# OpenBookReaderC_v26.net
KiCad netlist of a schematic drawn in EAGLE
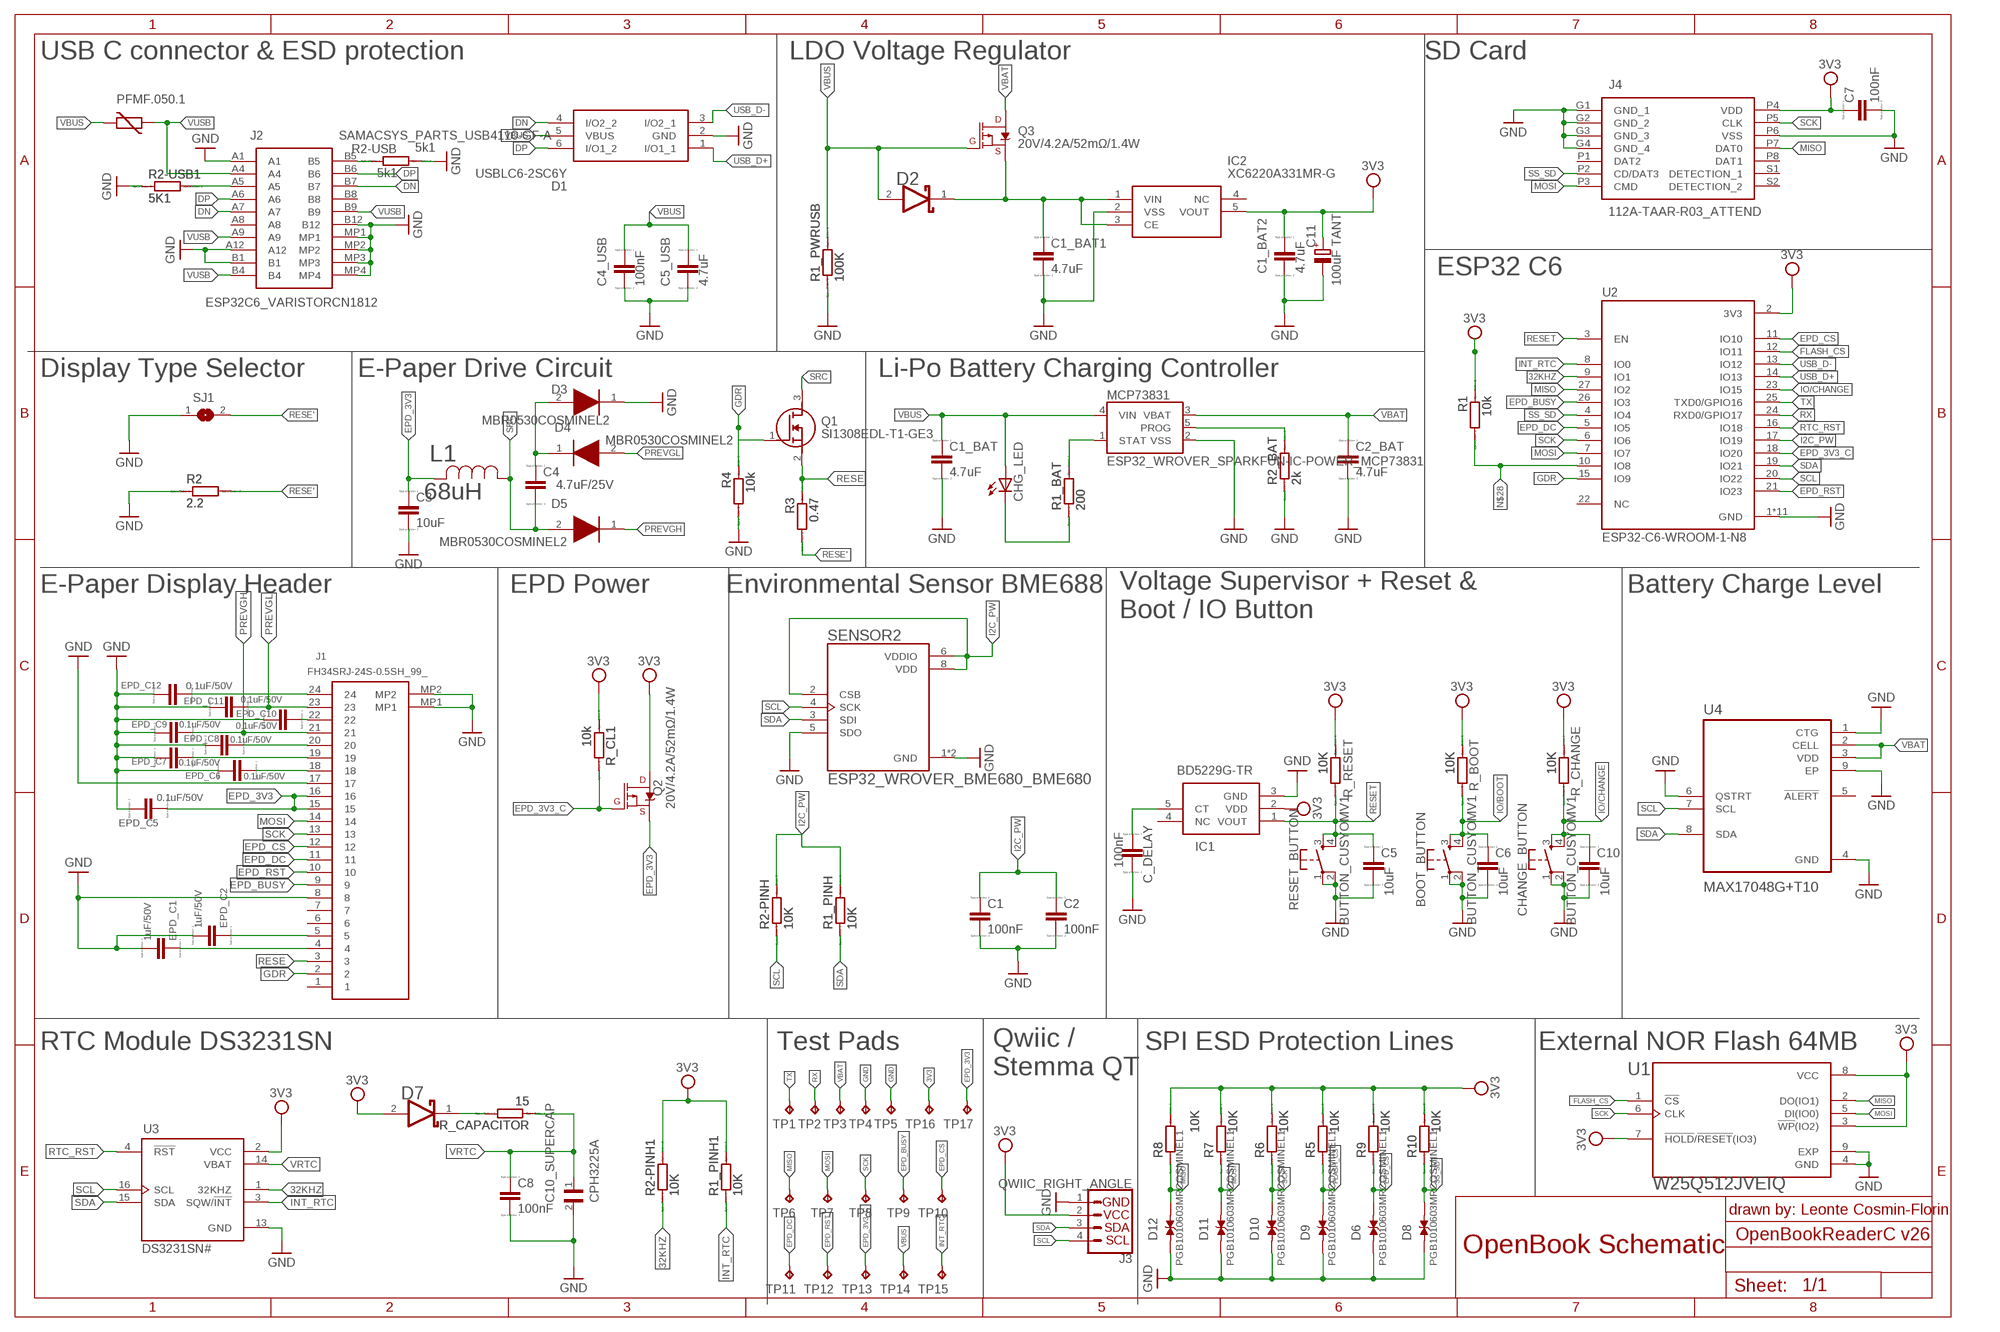
[diagram p0: schematic, sheet 1]

(export (version "E")
  (design (tool "Eeschema 10.0.6"))
  (components
    (comp (ref "BOOT_BUTTON")
      (value "BUTTON_CUSYOMV1")
      (footprint "eagle-import:MYBUTTON")
      (libsource (lib "eagle-import") (part "BUTTON_CUSYOMV1"))
    )
    (comp (ref "C1")
      (value "100nF")
      (footprint "eagle-import:ESP32_WROVER_EAGLE-LTSPICE_C0402")
      (libsource (lib "eagle-import") (part "ESP32_WROVER_EAGLE-LTSPICE_C"))
    )
    (comp (ref "C1_BAT")
      (value "4.7uF")
      (footprint "eagle-import:ESP32_WROVER_EAGLE-LTSPICE_C0402")
      (libsource (lib "eagle-import") (part "ESP32_WROVER_EAGLE-LTSPICE_C"))
    )
    (comp (ref "C1_BAT1")
      (value "4.7uF")
      (footprint "eagle-import:ESP32_WROVER_EAGLE-LTSPICE_C0402")
      (libsource (lib "eagle-import") (part "ESP32_WROVER_EAGLE-LTSPICE_C"))
    )
    (comp (ref "C1_BAT2")
      (value "4.7uF")
      (footprint "eagle-import:ESP32_WROVER_EAGLE-LTSPICE_C0402")
      (libsource (lib "eagle-import") (part "ESP32_WROVER_EAGLE-LTSPICE_C"))
    )
    (comp (ref "C2")
      (value "100nF")
      (footprint "eagle-import:ESP32_WROVER_EAGLE-LTSPICE_C0402")
      (libsource (lib "eagle-import") (part "ESP32_WROVER_EAGLE-LTSPICE_C"))
    )
    (comp (ref "C2_BAT")
      (value "4.7uF")
      (footprint "eagle-import:ESP32_WROVER_EAGLE-LTSPICE_C0402")
      (libsource (lib "eagle-import") (part "ESP32_WROVER_EAGLE-LTSPICE_C"))
    )
    (comp (ref "C3")
      (value "10uF")
      (footprint "eagle-import:ESP32_WROVER_EAGLE-LTSPICE_C0402")
      (libsource (lib "eagle-import") (part "ESP32_WROVER_EAGLE-LTSPICE_C"))
    )
    (comp (ref "C4")
      (value "4.7uF/25V")
      (footprint "eagle-import:ESP32_WROVER_EAGLE-LTSPICE_C0402")
      (libsource (lib "eagle-import") (part "ESP32_WROVER_EAGLE-LTSPICE_CC0402"))
    )
    (comp (ref "C4_USB")
      (value "100nF")
      (footprint "eagle-import:ESP32_WROVER_EAGLE-LTSPICE_C0402")
      (libsource (lib "eagle-import") (part "ESP32_WROVER_EAGLE-LTSPICE_C"))
    )
    (comp (ref "C5")
      (value "10uF")
      (footprint "eagle-import:ESP32_WROVER_EAGLE-LTSPICE_C0402")
      (libsource (lib "eagle-import") (part "ESP32_WROVER_EAGLE-LTSPICE_C"))
    )
    (comp (ref "C5_USB")
      (value "4.7uF")
      (footprint "eagle-import:ESP32_WROVER_EAGLE-LTSPICE_C0402")
      (libsource (lib "eagle-import") (part "ESP32_WROVER_EAGLE-LTSPICE_C"))
    )
    (comp (ref "C6")
      (value "10uF")
      (footprint "eagle-import:ESP32_WROVER_EAGLE-LTSPICE_C0402")
      (libsource (lib "eagle-import") (part "ESP32_WROVER_EAGLE-LTSPICE_C"))
    )
    (comp (ref "C7")
      (value "100nF")
      (footprint "eagle-import:ESP32_WROVER_EAGLE-LTSPICE_C0402")
      (libsource (lib "eagle-import") (part "ESP32_WROVER_EAGLE-LTSPICE_C"))
    )
    (comp (ref "C8")
      (value "100nF")
      (footprint "eagle-import:ESP32_WROVER_EAGLE-LTSPICE_C0402")
      (libsource (lib "eagle-import") (part "ESP32_WROVER_EAGLE-LTSPICE_C"))
    )
    (comp (ref "C10")
      (value "10uF")
      (footprint "eagle-import:ESP32_WROVER_EAGLE-LTSPICE_C0402")
      (libsource (lib "eagle-import") (part "ESP32_WROVER_EAGLE-LTSPICE_C"))
    )
    (comp (ref "C10_SUPERCAP")
      (value "CPH3225A")
      (footprint "eagle-import:CAPCP3225X100N")
      (fields (field (name "MF") "Seiko Instruments"))
      (libsource (lib "eagle-import") (part "CPH3225A"))
    )
    (comp (ref "C11")
      (value "100uF TANT")
      (footprint "eagle-import:RCL_CT3528")
      (libsource (lib "eagle-import") (part "RCL_CPOL-EUCT3528"))
    )
    (comp (ref "CHANGE_BUTTON")
      (value "BUTTON_CUSYOMV1")
      (footprint "eagle-import:MYBUTTON")
      (libsource (lib "eagle-import") (part "BUTTON_CUSYOMV1"))
    )
    (comp (ref "CHG_LED")
      (value "ADAFRUIT_LEDCHIP-LED0603")
      (footprint "eagle-import:ADAFRUIT_CHIP-LED0603")
      (libsource (lib "eagle-import") (part "ADAFRUIT_LEDCHIP-LED0603"))
    )
    (comp (ref "C_DELAY")
      (value "100nF")
      (footprint "eagle-import:ESP32_WROVER_EAGLE-LTSPICE_C0402")
      (libsource (lib "eagle-import") (part "ESP32_WROVER_EAGLE-LTSPICE_C"))
    )
    (comp (ref "D1")
      (value "USBLC6-2SC6Y")
      (footprint "eagle-import:SOT95P280X145-6N")
      (fields (field (name "MF") "STMicroelectronics"))
      (libsource (lib "eagle-import") (part "USBLC6-2SC6Y"))
    )
    (comp (ref "D2")
      (value "ESP32_WROVER_AVX---SD0805S020S1R0_AVX_SD0805S020S1R0_0_0AVX_SD0805S020S1R0_0_0")
      (footprint "eagle-import:ESP32_WROVER_AVX---SD0805S020S1R0_AVX_SD0805S020S1R0_0")
      (fields
        (field (name "DIGIKEY_PART_NUMBER") "478-7800-1-ND")
        (field (name "MF") "AVX")
        (field (name "MOUSER_PART_NUMBER") "581-SD0805S020S1R0")
      )
      (libsource (lib "eagle-import") (part "ESP32_WROVER_AVX---SD0805S020S1R0_AVX_SD0805S020S1R0_0_0AVX_SD0805S020S1R0_0_0"))
    )
    (comp (ref "D3")
      (value "MBR0530COSMINEL2")
      (footprint "eagle-import:SOD3716X135N")
      (libsource (lib "eagle-import") (part "MBR0530COSMINEL2"))
    )
    (comp (ref "D4")
      (value "MBR0530COSMINEL2")
      (footprint "eagle-import:SOD3716X135N")
      (libsource (lib "eagle-import") (part "MBR0530COSMINEL2"))
    )
    (comp (ref "D5")
      (value "MBR0530COSMINEL2")
      (footprint "eagle-import:SOD3716X135N")
      (libsource (lib "eagle-import") (part "MBR0530COSMINEL2"))
    )
    (comp (ref "D6")
      (value "PGB1010603MRCOSMINEL1")
      (footprint "eagle-import:DIOC1608X36N")
      (libsource (lib "eagle-import") (part "PGB1010603MRCOSMINEL1"))
    )
    (comp (ref "D7")
      (value "ESP32_WROVER_AVX---SD0805S020S1R0_AVX_SD0805S020S1R0_0_0AVX_SD0805S020S1R0_0_0")
      (footprint "eagle-import:ESP32_WROVER_AVX---SD0805S020S1R0_AVX_SD0805S020S1R0_0")
      (fields
        (field (name "DIGIKEY_PART_NUMBER") "478-7800-1-ND")
        (field (name "MF") "AVX")
        (field (name "MOUSER_PART_NUMBER") "581-SD0805S020S1R0")
      )
      (libsource (lib "eagle-import") (part "ESP32_WROVER_AVX---SD0805S020S1R0_AVX_SD0805S020S1R0_0_0AVX_SD0805S020S1R0_0_0"))
    )
    (comp (ref "D8")
      (value "PGB1010603MRCOSMINEL1")
      (footprint "eagle-import:DIOC1608X36N")
      (libsource (lib "eagle-import") (part "PGB1010603MRCOSMINEL1"))
    )
    (comp (ref "D9")
      (value "PGB1010603MRCOSMINEL1")
      (footprint "eagle-import:DIOC1608X36N")
      (libsource (lib "eagle-import") (part "PGB1010603MRCOSMINEL1"))
    )
    (comp (ref "D10")
      (value "PGB1010603MRCOSMINEL1")
      (footprint "eagle-import:DIOC1608X36N")
      (libsource (lib "eagle-import") (part "PGB1010603MRCOSMINEL1"))
    )
    (comp (ref "D11")
      (value "PGB1010603MRCOSMINEL1")
      (footprint "eagle-import:DIOC1608X36N")
      (libsource (lib "eagle-import") (part "PGB1010603MRCOSMINEL1"))
    )
    (comp (ref "D12")
      (value "PGB1010603MRCOSMINEL1")
      (footprint "eagle-import:DIOC1608X36N")
      (libsource (lib "eagle-import") (part "PGB1010603MRCOSMINEL1"))
    )
    (comp (ref "EPD_C1")
      (value "1uF/50V")
      (footprint "eagle-import:ESP32_WROVER_EAGLE-LTSPICE_C0402")
      (libsource (lib "eagle-import") (part "ESP32_WROVER_EAGLE-LTSPICE_C"))
    )
    (comp (ref "EPD_C2")
      (value "1uF/50V")
      (footprint "eagle-import:ESP32_WROVER_EAGLE-LTSPICE_C0402")
      (libsource (lib "eagle-import") (part "ESP32_WROVER_EAGLE-LTSPICE_C"))
    )
    (comp (ref "EPD_C5")
      (value "0.1uF/50V")
      (footprint "eagle-import:ESP32_WROVER_EAGLE-LTSPICE_C0402")
      (libsource (lib "eagle-import") (part "ESP32_WROVER_EAGLE-LTSPICE_C"))
    )
    (comp (ref "EPD_C6")
      (value "0.1uF/50V")
      (footprint "eagle-import:ESP32_WROVER_EAGLE-LTSPICE_C0402")
      (libsource (lib "eagle-import") (part "ESP32_WROVER_EAGLE-LTSPICE_C"))
    )
    (comp (ref "EPD_C7")
      (value "0.1uF/50V")
      (footprint "eagle-import:ESP32_WROVER_EAGLE-LTSPICE_C0402")
      (libsource (lib "eagle-import") (part "ESP32_WROVER_EAGLE-LTSPICE_C"))
    )
    (comp (ref "EPD_C8")
      (value "0.1uF/50V")
      (footprint "eagle-import:ESP32_WROVER_EAGLE-LTSPICE_C0402")
      (libsource (lib "eagle-import") (part "ESP32_WROVER_EAGLE-LTSPICE_C"))
    )
    (comp (ref "EPD_C9")
      (value "0.1uF/50V")
      (footprint "eagle-import:ESP32_WROVER_EAGLE-LTSPICE_C0402")
      (libsource (lib "eagle-import") (part "ESP32_WROVER_EAGLE-LTSPICE_C"))
    )
    (comp (ref "EPD_C10")
      (value "0.1uF/50V")
      (footprint "eagle-import:ESP32_WROVER_EAGLE-LTSPICE_C0402")
      (libsource (lib "eagle-import") (part "ESP32_WROVER_EAGLE-LTSPICE_C"))
    )
    (comp (ref "EPD_C11")
      (value "0.1uF/50V")
      (footprint "eagle-import:ESP32_WROVER_EAGLE-LTSPICE_C0402")
      (libsource (lib "eagle-import") (part "ESP32_WROVER_EAGLE-LTSPICE_C"))
    )
    (comp (ref "EPD_C12")
      (value "0.1uF/50V")
      (footprint "eagle-import:ESP32_WROVER_EAGLE-LTSPICE_C0402")
      (libsource (lib "eagle-import") (part "ESP32_WROVER_EAGLE-LTSPICE_C"))
    )
    (comp (ref "IC1")
      (value "BD5229G-TR")
      (footprint "eagle-import:SOT95P280X125-5N")
      (fields (field (name "MOUSER_PART_NUMBER") "755-BD5229G-TR"))
      (libsource (lib "eagle-import") (part "BD5229G-TR"))
    )
    (comp (ref "IC2")
      (value "XC6220A331MR-G")
      (footprint "eagle-import:SOT95P280X120-5N")
      (fields (field (name "MOUSER_PART_NUMBER") "865-XC6220A331MR-G"))
      (libsource (lib "eagle-import") (part "XC6220A331MR-G"))
    )
    (comp (ref "J1")
      (value "FH34SRJ-24S-0.5SH_99_")
      (footprint "eagle-import:FH34SRJ24S05SH99")
      (fields
        (field (name "MANUFACTURER_PART_NUMBER") "FH34SRJ-24S-0.5SH(99)")
        (field (name "MOUSER_PART_NUMBER") "798-FH34SRJ24S05SH99")
      )
      (libsource (lib "eagle-import") (part "FH34SRJ-24S-0.5SH_99_"))
    )
    (comp (ref "J2")
      (value "SAMACSYS_PARTS_USB4110-GF-A")
      (footprint "eagle-import:SAMACSYS_PARTS_USB4110GFA")
      (fields
        (field (name "MANUFACTURER_PART_NUMBER") "USB4110-GF-A")
        (field (name "MOUSER_PART_NUMBER") "640-USB4110-GF-A")
      )
      (libsource (lib "eagle-import") (part "SAMACSYS_PARTS_USB4110-GF-A"))
    )
    (comp (ref "J3")
      (value "QWIIC_RIGHT_ANGLE")
      (footprint "eagle-import:JST04_1MM_RA")
      (libsource (lib "eagle-import") (part "QWIIC_CONNECTORJS-1MM"))
    )
    (comp (ref "J4")
      (value "112A-TAAR-R03_ATTEND")
      (footprint "eagle-import:112ATAARR03ATTEND")
      (fields (field (name "MANUFACTURER_PART_NUMBER") "112A-TAAR-R03 ATTEND"))
      (libsource (lib "eagle-import") (part "112A-TAAR-R03_ATTEND"))
    )
    (comp (ref "L1")
      (value "68uH")
      (footprint "eagle-import:IND_4828-WE-TPC_WRE")
      (fields
        (field (name "MANUFACTURER_PART_NUMBER") "744043680")
        (field (name "COPYRIGHT") "Copyright (C) 2024 Ultra Librarian. All rights reserved.")
      )
      (libsource (lib "eagle-import") (part "744043680IND_4828-WE-TPC_WRE"))
    )
    (comp (ref "MCP73831")
      (value "ESP32_WROVER_SPARKFUN-IC-POWER_MCP73831")
      (footprint "eagle-import:ESP32_WROVER_SPARKFUN-IC-POWER_SOT23-5")
      (libsource (lib "eagle-import") (part "ESP32_WROVER_SPARKFUN-IC-POWER_MCP73831"))
    )
    (comp (ref "PFMF.050.1")
      (value "ESP32C6_VARISTORCN1812")
      (footprint "eagle-import:ESP32C6_VARISTOR_CT_CN1812")
      (libsource (lib "eagle-import") (part "ESP32C6_VARISTORCN1812"))
    )
    (comp (ref "Q1")
      (value "SI1308EDL-T1-GE3")
      (footprint "eagle-import:SOT65P210X110-3N")
      (fields (field (name "MF") "Vishay Siliconix"))
      (libsource (lib "eagle-import") (part "SI1308EDL-T1-GE3"))
    )
    (comp (ref "Q2")
      (value "20V/4.2A/52mΩ/1.4W")
      (footprint "eagle-import:ESP32_WROVER_SPARKFUN-DISCRETESEMI_SOT23-3")
      (libsource (lib "eagle-import") (part "ESP32_WROVER_SPARKFUN-DISCRETESEMI_MOSFET_PCH-DMG2305UX-7"))
    )
    (comp (ref "Q3")
      (value "20V/4.2A/52mΩ/1.4W")
      (footprint "eagle-import:ESP32_WROVER_SPARKFUN-DISCRETESEMI_SOT23-3")
      (libsource (lib "eagle-import") (part "ESP32_WROVER_SPARKFUN-DISCRETESEMI_MOSFET_PCH-DMG2305UX-7"))
    )
    (comp (ref "R1")
      (value "10k")
      (footprint "eagle-import:ESP32_WROVER_EAGLE-LTSPICE_R0402")
      (libsource (lib "eagle-import") (part "ESP32_WROVER_EAGLE-LTSPICE_RR0402"))
    )
    (comp (ref "R1_BAT")
      (value "200")
      (footprint "eagle-import:ESP32_WROVER_EAGLE-LTSPICE_R0402")
      (libsource (lib "eagle-import") (part "ESP32_WROVER_EAGLE-LTSPICE_RR0402"))
    )
    (comp (ref "R1_PINH")
      (value "10K")
      (footprint "eagle-import:ESP32_WROVER_EAGLE-LTSPICE_R0402")
      (libsource (lib "eagle-import") (part "ESP32_WROVER_EAGLE-LTSPICE_RR0402"))
    )
    (comp (ref "R1_PINH1")
      (value "10K")
      (footprint "eagle-import:ESP32_WROVER_EAGLE-LTSPICE_R0402")
      (libsource (lib "eagle-import") (part "ESP32_WROVER_EAGLE-LTSPICE_RR0402"))
    )
    (comp (ref "R1_PWRUSB")
      (value "100K")
      (footprint "eagle-import:ESP32_WROVER_EAGLE-LTSPICE_R0402")
      (libsource (lib "eagle-import") (part "ESP32_WROVER_EAGLE-LTSPICE_RR0402"))
    )
    (comp (ref "R2")
      (value "2.2")
      (footprint "eagle-import:ESP32_WROVER_EAGLE-LTSPICE_R0402")
      (libsource (lib "eagle-import") (part "ESP32_WROVER_EAGLE-LTSPICE_RR0402"))
    )
    (comp (ref "R2-PINH")
      (value "10K")
      (footprint "eagle-import:ESP32_WROVER_EAGLE-LTSPICE_R0402")
      (libsource (lib "eagle-import") (part "ESP32_WROVER_EAGLE-LTSPICE_RR0402"))
    )
    (comp (ref "R2-PINH1")
      (value "10K")
      (footprint "eagle-import:ESP32_WROVER_EAGLE-LTSPICE_R0402")
      (libsource (lib "eagle-import") (part "ESP32_WROVER_EAGLE-LTSPICE_RR0402"))
    )
    (comp (ref "R2-USB")
      (value "5k1")
      (footprint "eagle-import:ESP32_WROVER_EAGLE-LTSPICE_R0402")
      (libsource (lib "eagle-import") (part "ESP32_WROVER_EAGLE-LTSPICE_RR0402"))
    )
    (comp (ref "R2-USB1")
      (value "5K1")
      (footprint "eagle-import:ESP32_WROVER_EAGLE-LTSPICE_R0402")
      (libsource (lib "eagle-import") (part "ESP32_WROVER_EAGLE-LTSPICE_RR0402"))
    )
    (comp (ref "R2_BAT")
      (value "2k")
      (footprint "eagle-import:ESP32_WROVER_EAGLE-LTSPICE_R0402")
      (libsource (lib "eagle-import") (part "ESP32_WROVER_EAGLE-LTSPICE_RR0402"))
    )
    (comp (ref "R3")
      (value "0.47")
      (footprint "eagle-import:ESP32_WROVER_EAGLE-LTSPICE_R0402")
      (libsource (lib "eagle-import") (part "ESP32_WROVER_EAGLE-LTSPICE_R"))
    )
    (comp (ref "R4")
      (value "10k")
      (footprint "eagle-import:ESP32_WROVER_EAGLE-LTSPICE_R0402")
      (libsource (lib "eagle-import") (part "ESP32_WROVER_EAGLE-LTSPICE_R"))
    )
    (comp (ref "R5")
      (value "10K")
      (footprint "eagle-import:ESP32_WROVER_EAGLE-LTSPICE_R0402")
      (libsource (lib "eagle-import") (part "ESP32_WROVER_EAGLE-LTSPICE_RR0402"))
    )
    (comp (ref "R6")
      (value "10K")
      (footprint "eagle-import:ESP32_WROVER_EAGLE-LTSPICE_R0402")
      (libsource (lib "eagle-import") (part "ESP32_WROVER_EAGLE-LTSPICE_RR0402"))
    )
    (comp (ref "R7")
      (value "10K")
      (footprint "eagle-import:ESP32_WROVER_EAGLE-LTSPICE_R0402")
      (libsource (lib "eagle-import") (part "ESP32_WROVER_EAGLE-LTSPICE_RR0402"))
    )
    (comp (ref "R8")
      (value "10K")
      (footprint "eagle-import:ESP32_WROVER_EAGLE-LTSPICE_R0402")
      (libsource (lib "eagle-import") (part "ESP32_WROVER_EAGLE-LTSPICE_RR0402"))
    )
    (comp (ref "R9")
      (value "10K")
      (footprint "eagle-import:ESP32_WROVER_EAGLE-LTSPICE_R0402")
      (libsource (lib "eagle-import") (part "ESP32_WROVER_EAGLE-LTSPICE_RR0402"))
    )
    (comp (ref "R10")
      (value "10K")
      (footprint "eagle-import:ESP32_WROVER_EAGLE-LTSPICE_R0402")
      (libsource (lib "eagle-import") (part "ESP32_WROVER_EAGLE-LTSPICE_RR0402"))
    )
    (comp (ref "RESET_BUTTON")
      (value "BUTTON_CUSYOMV1")
      (footprint "eagle-import:MYBUTTON")
      (libsource (lib "eagle-import") (part "BUTTON_CUSYOMV1"))
    )
    (comp (ref "R_BOOT")
      (value "10K")
      (footprint "eagle-import:ESP32_WROVER_EAGLE-LTSPICE_R0402")
      (libsource (lib "eagle-import") (part "ESP32_WROVER_EAGLE-LTSPICE_RR0402"))
    )
    (comp (ref "R_CAPACITOR")
      (value "15")
      (footprint "eagle-import:ESP32_WROVER_EAGLE-LTSPICE_R0402")
      (libsource (lib "eagle-import") (part "ESP32_WROVER_EAGLE-LTSPICE_RR0402"))
    )
    (comp (ref "R_CHANGE")
      (value "10K")
      (footprint "eagle-import:ESP32_WROVER_EAGLE-LTSPICE_R0402")
      (libsource (lib "eagle-import") (part "ESP32_WROVER_EAGLE-LTSPICE_RR0402"))
    )
    (comp (ref "R_CL1")
      (value "10k")
      (footprint "eagle-import:ESP32_WROVER_EAGLE-LTSPICE_R0402")
      (libsource (lib "eagle-import") (part "ESP32_WROVER_EAGLE-LTSPICE_RR0402"))
    )
    (comp (ref "R_RESET")
      (value "10K")
      (footprint "eagle-import:ESP32_WROVER_EAGLE-LTSPICE_R0402")
      (libsource (lib "eagle-import") (part "ESP32_WROVER_EAGLE-LTSPICE_RR0402"))
    )
    (comp (ref "SENSOR2")
      (value "ESP32_WROVER_BME680_BME680")
      (footprint "eagle-import:ESP32_WROVER_BME680_PSON80P300X300X100-8N")
      (fields (field (name "MF") "Bosch Sensortec") (field (name "MP") "BME680"))
      (libsource (lib "eagle-import") (part "ESP32_WROVER_BME680_BME680"))
    )
    (comp (ref "SJ1") (value "SJ") (footprint "eagle-import:SJ") (libsource (lib "eagle-import") (part "SJ")))
    (comp (ref "TP1")
      (value "TP")
      (footprint "eagle-import:TP20R")
      (libsource (lib "eagle-import") (part "TP"))
    )
    (comp (ref "TP2")
      (value "TP")
      (footprint "eagle-import:TP20R")
      (libsource (lib "eagle-import") (part "TP"))
    )
    (comp (ref "TP3")
      (value "TP")
      (footprint "eagle-import:TP20R")
      (libsource (lib "eagle-import") (part "TP"))
    )
    (comp (ref "TP4")
      (value "TP")
      (footprint "eagle-import:TP20R")
      (libsource (lib "eagle-import") (part "TP"))
    )
    (comp (ref "TP5")
      (value "TP")
      (footprint "eagle-import:TP20R")
      (libsource (lib "eagle-import") (part "TP"))
    )
    (comp (ref "TP6")
      (value "TP")
      (footprint "eagle-import:TP20R")
      (libsource (lib "eagle-import") (part "TP"))
    )
    (comp (ref "TP7")
      (value "TP")
      (footprint "eagle-import:TP20R")
      (libsource (lib "eagle-import") (part "TP"))
    )
    (comp (ref "TP8")
      (value "TP")
      (footprint "eagle-import:TP20R")
      (libsource (lib "eagle-import") (part "TP"))
    )
    (comp (ref "TP9")
      (value "TP")
      (footprint "eagle-import:TP20R")
      (libsource (lib "eagle-import") (part "TP"))
    )
    (comp (ref "TP10")
      (value "TP")
      (footprint "eagle-import:TP20R")
      (libsource (lib "eagle-import") (part "TP"))
    )
    (comp (ref "TP11")
      (value "TP")
      (footprint "eagle-import:TP20R")
      (libsource (lib "eagle-import") (part "TP"))
    )
    (comp (ref "TP12")
      (value "TP")
      (footprint "eagle-import:TP20R")
      (libsource (lib "eagle-import") (part "TP"))
    )
    (comp (ref "TP13")
      (value "TP")
      (footprint "eagle-import:TP20R")
      (libsource (lib "eagle-import") (part "TP"))
    )
    (comp (ref "TP14")
      (value "TP")
      (footprint "eagle-import:TP20R")
      (libsource (lib "eagle-import") (part "TP"))
    )
    (comp (ref "TP15")
      (value "TP")
      (footprint "eagle-import:TP20R")
      (libsource (lib "eagle-import") (part "TP"))
    )
    (comp (ref "TP16")
      (value "TP")
      (footprint "eagle-import:TP20R")
      (libsource (lib "eagle-import") (part "TP"))
    )
    (comp (ref "TP17")
      (value "TP")
      (footprint "eagle-import:TP20R")
      (libsource (lib "eagle-import") (part "TP"))
    )
    (comp (ref "U1")
      (value "W25Q512JVEIQ")
      (footprint "eagle-import:SON127P600X800X80-9N")
      (fields (field (name "MF") "Winbond Electronics"))
      (libsource (lib "eagle-import") (part "W25Q512JVEIQ"))
    )
    (comp (ref "U2")
      (value "ESP32-C6-WROOM-1-N8")
      (footprint "eagle-import:XCVR_ESP32-C6-WROOM-1-N8")
      (fields (field (name "MF") "Espressif Systems"))
      (libsource (lib "eagle-import") (part "ESP32-C6-WROOM-1-N8"))
    )
    (comp (ref "U3")
      (value "DS3231SN#")
      (footprint "eagle-import:SOIC127P1032X265-16N")
      (fields (field (name "MF") "Analog Devices"))
      (libsource (lib "eagle-import") (part "DS3231SN#"))
    )
    (comp (ref "U4")
      (value "MAX17048G+T10")
      (footprint "eagle-import:SON50P200X200X80-9N")
      (fields (field (name "MF") "Analog Devices"))
      (libsource (lib "eagle-import") (part "MAX17048G+T10"))
    )
  )
  (nets
    (net (code "1") (name "3V3") (class "Default")
      (node (ref "C11") (pin "+") (pinfunction "+_+") (pintype "passive"))
      (node (ref "C1_BAT2") (pin "1") (pinfunction "1_1") (pintype "passive"))
      (node (ref "C7") (pin "1") (pinfunction "1_1") (pintype "passive"))
      (node (ref "D7") (pin "2") (pinfunction "ANODE_2") (pintype "bidirectional"))
      (node (ref "IC1") (pin "2") (pinfunction "VDD_2") (pintype "bidirectional"))
      (node (ref "IC2") (pin "5") (pinfunction "VOUT_5") (pintype "bidirectional"))
      (node (ref "J3") (pin "2") (pinfunction "2_2") (pintype "power_in"))
      (node (ref "J4") (pin "P4") (pinfunction "VDD_P4") (pintype "bidirectional"))
      (node (ref "Q2") (pin "3") (pinfunction "D_3") (pintype "bidirectional"))
      (node (ref "R1") (pin "1") (pinfunction "1_1") (pintype "passive"))
      (node (ref "R10") (pin "2") (pinfunction "2_2") (pintype "passive"))
      (node (ref "R1_PINH1") (pin "2") (pinfunction "2_2") (pintype "passive"))
      (node (ref "R2-PINH1") (pin "2") (pinfunction "2_2") (pintype "passive"))
      (node (ref "R5") (pin "2") (pinfunction "2_2") (pintype "passive"))
      (node (ref "R6") (pin "2") (pinfunction "2_2") (pintype "passive"))
      (node (ref "R7") (pin "2") (pinfunction "2_2") (pintype "passive"))
      (node (ref "R8") (pin "2") (pinfunction "2_2") (pintype "passive"))
      (node (ref "R9") (pin "2") (pinfunction "2_2") (pintype "passive"))
      (node (ref "R_BOOT") (pin "1") (pinfunction "1_1") (pintype "passive"))
      (node (ref "R_CHANGE") (pin "1") (pinfunction "1_1") (pintype "passive"))
      (node (ref "R_CL1") (pin "1") (pinfunction "1_1") (pintype "passive"))
      (node (ref "R_RESET") (pin "1") (pinfunction "1_1") (pintype "passive"))
      (node (ref "TP16") (pin "TP") (pinfunction "TP_TP") (pintype "input"))
      (node (ref "U1") (pin "3") (pinfunction "~{WP}(IO2)_3") (pintype "bidirectional"))
      (node (ref "U1") (pin "7") (pinfunction "~{HOLD}/~{RESET}(IO3)_7") (pintype "bidirectional"))
      (node (ref "U1") (pin "8") (pinfunction "VCC_8") (pintype "power_in"))
      (node (ref "U2") (pin "2") (pinfunction "3V3_2") (pintype "power_in"))
      (node (ref "U3") (pin "2") (pinfunction "VCC_2") (pintype "power_in"))
    )
    (net (code "2") (name "32KHZ") (class "Default")
      (node (ref "R2-PINH1") (pin "1") (pinfunction "1_1") (pintype "passive"))
      (node (ref "U2") (pin "9") (pinfunction "IO1_9") (pintype "bidirectional"))
      (node (ref "U3") (pin "1") (pinfunction "32KHZ_1") (pintype "output"))
    )
    (net (code "3") (name "DN") (class "Default")
      (node (ref "D1") (pin "4") (pinfunction "I/O2_2_4") (pintype "bidirectional"))
      (node (ref "J2") (pin "A7") (pinfunction "A7_A7") (pintype "bidirectional"))
      (node (ref "J2") (pin "B7") (pinfunction "B7_B7") (pintype "bidirectional"))
    )
    (net (code "4") (name "DP") (class "Default")
      (node (ref "D1") (pin "6") (pinfunction "I/O1_2_6") (pintype "bidirectional"))
      (node (ref "J2") (pin "A6") (pinfunction "A6_A6") (pintype "bidirectional"))
      (node (ref "J2") (pin "B6") (pinfunction "B6_B6") (pintype "bidirectional"))
    )
    (net (code "5") (name "EPD_3V3") (class "Default")
      (node (ref "C3") (pin "1") (pinfunction "1_1") (pintype "passive"))
      (node (ref "EPD_C5") (pin "1") (pinfunction "1_1") (pintype "passive"))
      (node (ref "J1") (pin "15") (pinfunction "15_15") (pintype "bidirectional"))
      (node (ref "J1") (pin "16") (pinfunction "16_16") (pintype "bidirectional"))
      (node (ref "L1") (pin "2") (pinfunction "2_2") (pintype "passive"))
      (node (ref "Q2") (pin "2") (pinfunction "S_2") (pintype "bidirectional"))
      (node (ref "TP17") (pin "TP") (pinfunction "TP_TP") (pintype "input"))
    )
    (net (code "6") (name "EPD_3V3_C") (class "Default")
      (node (ref "Q2") (pin "1") (pinfunction "G_1") (pintype "bidirectional"))
      (node (ref "R_CL1") (pin "2") (pinfunction "2_2") (pintype "passive"))
      (node (ref "TP13") (pin "TP") (pinfunction "TP_TP") (pintype "input"))
      (node (ref "U2") (pin "18") (pinfunction "IO20_18") (pintype "bidirectional"))
    )
    (net (code "7") (name "EPD_BUSY") (class "Default")
      (node (ref "J1") (pin "9") (pinfunction "9_9") (pintype "bidirectional"))
      (node (ref "TP9") (pin "TP") (pinfunction "TP_TP") (pintype "input"))
      (node (ref "U2") (pin "26") (pinfunction "IO3_26") (pintype "bidirectional"))
    )
    (net (code "8") (name "EPD_CS") (class "Default")
      (node (ref "D6") (pin "2") (pinfunction "2_2") (pintype "passive"))
      (node (ref "J1") (pin "12") (pinfunction "12_12") (pintype "bidirectional"))
      (node (ref "R9") (pin "1") (pinfunction "1_1") (pintype "passive"))
      (node (ref "TP10") (pin "TP") (pinfunction "TP_TP") (pintype "input"))
      (node (ref "U2") (pin "11") (pinfunction "IO10_11") (pintype "bidirectional"))
    )
    (net (code "9") (name "EPD_DC") (class "Default")
      (node (ref "J1") (pin "11") (pinfunction "11_11") (pintype "bidirectional"))
      (node (ref "TP11") (pin "TP") (pinfunction "TP_TP") (pintype "input"))
      (node (ref "U2") (pin "5") (pinfunction "IO5_5") (pintype "bidirectional"))
    )
    (net (code "10") (name "EPD_RST") (class "Default")
      (node (ref "J1") (pin "10") (pinfunction "10_10") (pintype "bidirectional"))
      (node (ref "TP12") (pin "TP") (pinfunction "TP_TP") (pintype "input"))
      (node (ref "U2") (pin "21") (pinfunction "IO23_21") (pintype "bidirectional"))
    )
    (net (code "11") (name "FLASH_CS") (class "Default")
      (node (ref "D9") (pin "2") (pinfunction "2_2") (pintype "passive"))
      (node (ref "R5") (pin "1") (pinfunction "1_1") (pintype "passive"))
      (node (ref "U1") (pin "1") (pinfunction "~{CS}_1") (pintype "input"))
      (node (ref "U2") (pin "12") (pinfunction "IO11_12") (pintype "bidirectional"))
    )
    (net (code "12") (name "GDR") (class "Default")
      (node (ref "J1") (pin "2") (pinfunction "2_2") (pintype "bidirectional"))
      (node (ref "Q1") (pin "1") (pinfunction "G_1") (pintype "bidirectional"))
      (node (ref "R4") (pin "1") (pinfunction "1_1") (pintype "passive"))
      (node (ref "U2") (pin "15") (pinfunction "IO9_15") (pintype "bidirectional"))
    )
    (net (code "13") (name "GND") (class "Default")
      (node (ref "BOOT_BUTTON") (pin "1") (pinfunction "1_1") (pintype "passive"))
      (node (ref "BOOT_BUTTON") (pin "2") (pinfunction "2_2") (pintype "passive"))
      (node (ref "C1") (pin "2") (pinfunction "2_2") (pintype "passive"))
      (node (ref "C10") (pin "2") (pinfunction "2_2") (pintype "passive"))
      (node (ref "C10_SUPERCAP") (pin "2") (pinfunction "2_2") (pintype "passive"))
      (node (ref "C11") (pin "-") (pinfunction "-_-") (pintype "passive"))
      (node (ref "C1_BAT") (pin "2") (pinfunction "2_2") (pintype "passive"))
      (node (ref "C1_BAT1") (pin "2") (pinfunction "2_2") (pintype "passive"))
      (node (ref "C1_BAT2") (pin "2") (pinfunction "2_2") (pintype "passive"))
      (node (ref "C2") (pin "2") (pinfunction "2_2") (pintype "passive"))
      (node (ref "C2_BAT") (pin "2") (pinfunction "2_2") (pintype "passive"))
      (node (ref "C3") (pin "2") (pinfunction "2_2") (pintype "passive"))
      (node (ref "C4_USB") (pin "2") (pinfunction "2_2") (pintype "passive"))
      (node (ref "C5") (pin "2") (pinfunction "2_2") (pintype "passive"))
      (node (ref "C5_USB") (pin "2") (pinfunction "2_2") (pintype "passive"))
      (node (ref "C6") (pin "2") (pinfunction "2_2") (pintype "passive"))
      (node (ref "C7") (pin "2") (pinfunction "2_2") (pintype "passive"))
      (node (ref "C8") (pin "2") (pinfunction "2_2") (pintype "passive"))
      (node (ref "CHANGE_BUTTON") (pin "1") (pinfunction "1_1") (pintype "passive"))
      (node (ref "CHANGE_BUTTON") (pin "2") (pinfunction "2_2") (pintype "passive"))
      (node (ref "C_DELAY") (pin "2") (pinfunction "2_2") (pintype "passive"))
      (node (ref "D1") (pin "2") (pinfunction "GND_2") (pintype "bidirectional"))
      (node (ref "D10") (pin "1") (pinfunction "1_1") (pintype "passive"))
      (node (ref "D11") (pin "1") (pinfunction "1_1") (pintype "passive"))
      (node (ref "D12") (pin "1") (pinfunction "1_1") (pintype "passive"))
      (node (ref "D3") (pin "1") (pinfunction "K_1") (pintype "bidirectional"))
      (node (ref "D6") (pin "1") (pinfunction "1_1") (pintype "passive"))
      (node (ref "D8") (pin "1") (pinfunction "1_1") (pintype "passive"))
      (node (ref "D9") (pin "1") (pinfunction "1_1") (pintype "passive"))
      (node (ref "EPD_C1") (pin "2") (pinfunction "2_2") (pintype "passive"))
      (node (ref "EPD_C10") (pin "2") (pinfunction "2_2") (pintype "passive"))
      (node (ref "EPD_C11") (pin "2") (pinfunction "2_2") (pintype "passive"))
      (node (ref "EPD_C12") (pin "2") (pinfunction "2_2") (pintype "passive"))
      (node (ref "EPD_C2") (pin "2") (pinfunction "2_2") (pintype "passive"))
      (node (ref "EPD_C5") (pin "2") (pinfunction "2_2") (pintype "passive"))
      (node (ref "EPD_C6") (pin "2") (pinfunction "2_2") (pintype "passive"))
      (node (ref "EPD_C7") (pin "2") (pinfunction "2_2") (pintype "passive"))
      (node (ref "EPD_C8") (pin "2") (pinfunction "2_2") (pintype "passive"))
      (node (ref "EPD_C9") (pin "2") (pinfunction "2_2") (pintype "passive"))
      (node (ref "IC1") (pin "3") (pinfunction "GND_3") (pintype "bidirectional"))
      (node (ref "IC2") (pin "2") (pinfunction "VSS_2") (pintype "bidirectional"))
      (node (ref "J1") (pin "17") (pinfunction "17_17") (pintype "bidirectional"))
      (node (ref "J1") (pin "8") (pinfunction "8_8") (pintype "bidirectional"))
      (node (ref "J1") (pin "MP1") (pinfunction "MP1_MP1") (pintype "bidirectional"))
      (node (ref "J1") (pin "MP2") (pinfunction "MP2_MP2") (pintype "bidirectional"))
      (node (ref "J2") (pin "A1") (pinfunction "A1_A1") (pintype "bidirectional"))
      (node (ref "J2") (pin "A12") (pinfunction "A12_A12") (pintype "bidirectional"))
      (node (ref "J2") (pin "B1") (pinfunction "B1_B1") (pintype "bidirectional"))
      (node (ref "J2") (pin "B12") (pinfunction "B12_B12") (pintype "bidirectional"))
      (node (ref "J2") (pin "MP1") (pinfunction "MP1_MP1") (pintype "bidirectional"))
      (node (ref "J2") (pin "MP2") (pinfunction "MP2_MP2") (pintype "bidirectional"))
      (node (ref "J2") (pin "MP3") (pinfunction "MP3_MP3") (pintype "bidirectional"))
      (node (ref "J2") (pin "MP4") (pinfunction "MP4_MP4") (pintype "bidirectional"))
      (node (ref "J3") (pin "1") (pinfunction "1_1") (pintype "power_in"))
      (node (ref "J4") (pin "G1") (pinfunction "GND_1_G1") (pintype "bidirectional"))
      (node (ref "J4") (pin "G2") (pinfunction "GND_2_G2") (pintype "bidirectional"))
      (node (ref "J4") (pin "G3") (pinfunction "GND_3_G3") (pintype "bidirectional"))
      (node (ref "J4") (pin "G4") (pinfunction "GND_4_G4") (pintype "bidirectional"))
      (node (ref "J4") (pin "P6") (pinfunction "VSS_P6") (pintype "bidirectional"))
      (node (ref "MCP73831") (pin "2") (pinfunction "VSS_2") (pintype "power_in"))
      (node (ref "R1_PWRUSB") (pin "1") (pinfunction "1_1") (pintype "passive"))
      (node (ref "R2") (pin "1") (pinfunction "1_1") (pintype "passive"))
      (node (ref "R2-USB") (pin "2") (pinfunction "2_2") (pintype "passive"))
      (node (ref "R2-USB1") (pin "1") (pinfunction "1_1") (pintype "passive"))
      (node (ref "R2_BAT") (pin "1") (pinfunction "1_1") (pintype "passive"))
      (node (ref "R4") (pin "2") (pinfunction "2_2") (pintype "passive"))
      (node (ref "RESET_BUTTON") (pin "1") (pinfunction "1_1") (pintype "passive"))
      (node (ref "RESET_BUTTON") (pin "2") (pinfunction "2_2") (pintype "passive"))
      (node (ref "SENSOR2") (pin "1") (pinfunction "GND_1") (pintype "power_in"))
      (node (ref "SENSOR2") (pin "5") (pinfunction "SDO_5") (pintype "bidirectional"))
      (node (ref "SENSOR2") (pin "7") (pinfunction "GND_7") (pintype "power_in"))
      (node (ref "SJ1") (pin "1") (pinfunction "1_1") (pintype "passive"))
      (node (ref "TP4") (pin "TP") (pinfunction "TP_TP") (pintype "input"))
      (node (ref "TP5") (pin "TP") (pinfunction "TP_TP") (pintype "input"))
      (node (ref "U1") (pin "4") (pinfunction "GND_4") (pintype "power_in"))
      (node (ref "U1") (pin "9") (pinfunction "EXP_9") (pintype "passive"))
      (node (ref "U2") (pin "1") (pinfunction "GND_1") (pintype "power_in"))
      (node (ref "U2") (pin "28") (pinfunction "GND_28") (pintype "power_in"))
      (node (ref "U2") (pin "29_1") (pinfunction "GND_29_1") (pintype "power_in"))
      (node (ref "U2") (pin "29_2") (pinfunction "GND_29_2") (pintype "power_in"))
      (node (ref "U2") (pin "29_3") (pinfunction "GND_29_3") (pintype "power_in"))
      (node (ref "U2") (pin "29_4") (pinfunction "GND_29_4") (pintype "power_in"))
      (node (ref "U2") (pin "29_5") (pinfunction "GND_29_5") (pintype "power_in"))
      (node (ref "U2") (pin "29_6") (pinfunction "GND_29_6") (pintype "power_in"))
      (node (ref "U2") (pin "29_7") (pinfunction "GND_29_7") (pintype "power_in"))
      (node (ref "U2") (pin "29_8") (pinfunction "GND_29_8") (pintype "power_in"))
      (node (ref "U2") (pin "29_9") (pinfunction "GND_29_9") (pintype "power_in"))
      (node (ref "U3") (pin "13") (pinfunction "GND_13") (pintype "power_in"))
      (node (ref "U4") (pin "1") (pinfunction "CTG_1") (pintype "power_in"))
      (node (ref "U4") (pin "4") (pinfunction "GND_4") (pintype "power_in"))
      (node (ref "U4") (pin "6") (pinfunction "QSTRT_6") (pintype "input"))
      (node (ref "U4") (pin "9") (pinfunction "EP_9") (pintype "power_in"))
    )
    (net (code "14") (name "I2C_PW") (class "Default")
      (node (ref "C1") (pin "1") (pinfunction "1_1") (pintype "passive"))
      (node (ref "C2") (pin "1") (pinfunction "1_1") (pintype "passive"))
      (node (ref "R1_PINH") (pin "2") (pinfunction "2_2") (pintype "passive"))
      (node (ref "R2-PINH") (pin "2") (pinfunction "2_2") (pintype "passive"))
      (node (ref "SENSOR2") (pin "2") (pinfunction "CSB_2") (pintype "input"))
      (node (ref "SENSOR2") (pin "6") (pinfunction "VDDIO_6") (pintype "power_in"))
      (node (ref "SENSOR2") (pin "8") (pinfunction "VDD_8") (pintype "power_in"))
      (node (ref "U2") (pin "17") (pinfunction "IO19_17") (pintype "bidirectional"))
    )
    (net (code "15") (name "INT_RTC") (class "Default")
      (node (ref "R1_PINH1") (pin "1") (pinfunction "1_1") (pintype "passive"))
      (node (ref "TP15") (pin "TP") (pinfunction "TP_TP") (pintype "input"))
      (node (ref "U2") (pin "8") (pinfunction "IO0_8") (pintype "bidirectional"))
      (node (ref "U3") (pin "3") (pinfunction "SQW/~{INT}_3") (pintype "output"))
    )
    (net (code "16") (name "IO{slash}BOOT") (class "Default")
      (node (ref "BOOT_BUTTON") (pin "3") (pinfunction "3_3") (pintype "passive"))
      (node (ref "BOOT_BUTTON") (pin "4") (pinfunction "4_4") (pintype "passive"))
      (node (ref "C6") (pin "1") (pinfunction "1_1") (pintype "passive"))
      (node (ref "R_BOOT") (pin "2") (pinfunction "2_2") (pintype "passive"))
    )
    (net (code "17") (name "IO{slash}CHANGE") (class "Default")
      (node (ref "C10") (pin "1") (pinfunction "1_1") (pintype "passive"))
      (node (ref "CHANGE_BUTTON") (pin "3") (pinfunction "3_3") (pintype "passive"))
      (node (ref "CHANGE_BUTTON") (pin "4") (pinfunction "4_4") (pintype "passive"))
      (node (ref "R_CHANGE") (pin "2") (pinfunction "2_2") (pintype "passive"))
      (node (ref "U2") (pin "23") (pinfunction "IO15_23") (pintype "bidirectional"))
    )
    (net (code "18") (name "MISO") (class "Default")
      (node (ref "D12") (pin "2") (pinfunction "2_2") (pintype "passive"))
      (node (ref "J4") (pin "P7") (pinfunction "DAT0_P7") (pintype "bidirectional"))
      (node (ref "R8") (pin "1") (pinfunction "1_1") (pintype "passive"))
      (node (ref "TP6") (pin "TP") (pinfunction "TP_TP") (pintype "input"))
      (node (ref "U1") (pin "2") (pinfunction "DO(IO1)_2") (pintype "bidirectional"))
      (node (ref "U2") (pin "27") (pinfunction "IO2_27") (pintype "bidirectional"))
    )
    (net (code "19") (name "MOSI") (class "Default")
      (node (ref "D11") (pin "2") (pinfunction "2_2") (pintype "passive"))
      (node (ref "J1") (pin "14") (pinfunction "14_14") (pintype "bidirectional"))
      (node (ref "J4") (pin "P3") (pinfunction "CMD_P3") (pintype "bidirectional"))
      (node (ref "R7") (pin "1") (pinfunction "1_1") (pintype "passive"))
      (node (ref "TP7") (pin "TP") (pinfunction "TP_TP") (pintype "input"))
      (node (ref "U1") (pin "5") (pinfunction "DI(IO0)_5") (pintype "bidirectional"))
      (node (ref "U2") (pin "7") (pinfunction "IO7_7") (pintype "bidirectional"))
    )
    (net (code "20") (name "N$28") (class "Default")
      (node (ref "R1") (pin "2") (pinfunction "2_2") (pintype "passive"))
      (node (ref "U2") (pin "10") (pinfunction "IO8_10") (pintype "bidirectional"))
    )
    (net (code "21") (name "Net-(CHG_LED-PadC)") (class "Default")
      (node (ref "CHG_LED") (pin "C") (pinfunction "C_C") (pintype "passive"))
      (node (ref "R1_BAT") (pin "1") (pinfunction "1_1") (pintype "passive"))
    )
    (net (code "22") (name "Net-(D2-CATHODE)") (class "Default")
      (node (ref "C1_BAT1") (pin "1") (pinfunction "1_1") (pintype "passive"))
      (node (ref "D2") (pin "1") (pinfunction "CATHODE_1") (pintype "bidirectional"))
      (node (ref "IC2") (pin "1") (pinfunction "VIN_1") (pintype "bidirectional"))
      (node (ref "IC2") (pin "3") (pinfunction "CE_3") (pintype "bidirectional"))
      (node (ref "Q3") (pin "2") (pinfunction "S_2") (pintype "bidirectional"))
    )
    (net (code "23") (name "Net-(D3-A)") (class "Default")
      (node (ref "C4") (pin "1") (pinfunction "1_1") (pintype "passive"))
      (node (ref "D3") (pin "2") (pinfunction "A_2") (pintype "bidirectional"))
      (node (ref "D4") (pin "1") (pinfunction "K_1") (pintype "bidirectional"))
    )
    (net (code "24") (name "Net-(D7-CATHODE)") (class "Default")
      (node (ref "D7") (pin "1") (pinfunction "CATHODE_1") (pintype "bidirectional"))
      (node (ref "R_CAPACITOR") (pin "2") (pinfunction "2_2") (pintype "passive"))
    )
    (net (code "25") (name "Net-(EPD_C1-Pad1)") (class "Default")
      (node (ref "EPD_C1") (pin "1") (pinfunction "1_1") (pintype "passive"))
      (node (ref "J1") (pin "4") (pinfunction "4_4") (pintype "bidirectional"))
    )
    (net (code "26") (name "Net-(EPD_C2-Pad1)") (class "Default")
      (node (ref "EPD_C2") (pin "1") (pinfunction "1_1") (pintype "passive"))
      (node (ref "J1") (pin "5") (pinfunction "5_5") (pintype "bidirectional"))
    )
    (net (code "27") (name "Net-(EPD_C6-Pad1)") (class "Default")
      (node (ref "EPD_C6") (pin "1") (pinfunction "1_1") (pintype "passive"))
      (node (ref "J1") (pin "18") (pinfunction "18_18") (pintype "bidirectional"))
    )
    (net (code "28") (name "Net-(EPD_C7-Pad1)") (class "Default")
      (node (ref "EPD_C7") (pin "1") (pinfunction "1_1") (pintype "passive"))
      (node (ref "J1") (pin "19") (pinfunction "19_19") (pintype "bidirectional"))
    )
    (net (code "29") (name "Net-(EPD_C8-Pad1)") (class "Default")
      (node (ref "EPD_C8") (pin "1") (pinfunction "1_1") (pintype "passive"))
      (node (ref "J1") (pin "20") (pinfunction "20_20") (pintype "bidirectional"))
    )
    (net (code "30") (name "Net-(EPD_C10-Pad1)") (class "Default")
      (node (ref "EPD_C10") (pin "1") (pinfunction "1_1") (pintype "passive"))
      (node (ref "J1") (pin "22") (pinfunction "22_22") (pintype "bidirectional"))
    )
    (net (code "31") (name "Net-(EPD_C12-Pad1)") (class "Default")
      (node (ref "EPD_C12") (pin "1") (pinfunction "1_1") (pintype "passive"))
      (node (ref "J1") (pin "24") (pinfunction "24_24") (pintype "bidirectional"))
    )
    (net (code "32") (name "Net-(IC1-CT)") (class "Default")
      (node (ref "C_DELAY") (pin "1") (pinfunction "1_1") (pintype "passive"))
      (node (ref "IC1") (pin "5") (pinfunction "CT_5") (pintype "bidirectional"))
    )
    (net (code "33") (name "Net-(J2-PadA5)") (class "Default")
      (node (ref "J2") (pin "A5") (pinfunction "A5_A5") (pintype "bidirectional"))
      (node (ref "R2-USB1") (pin "2") (pinfunction "2_2") (pintype "passive"))
    )
    (net (code "34") (name "Net-(J2-PadB5)") (class "Default")
      (node (ref "J2") (pin "B5") (pinfunction "B5_B5") (pintype "bidirectional"))
      (node (ref "R2-USB") (pin "1") (pinfunction "1_1") (pintype "passive"))
    )
    (net (code "35") (name "Net-(MCP73831-PROG)") (class "Default")
      (node (ref "MCP73831") (pin "5") (pinfunction "PROG_5") (pintype "input"))
      (node (ref "R2_BAT") (pin "2") (pinfunction "2_2") (pintype "passive"))
    )
    (net (code "36") (name "Net-(MCP73831-STAT)") (class "Default")
      (node (ref "MCP73831") (pin "1") (pinfunction "STAT_1") (pintype "output"))
      (node (ref "R1_BAT") (pin "2") (pinfunction "2_2") (pintype "passive"))
    )
    (net (code "37") (name "PREVGH") (class "Default")
      (node (ref "D5") (pin "1") (pinfunction "K_1") (pintype "bidirectional"))
      (node (ref "EPD_C9") (pin "1") (pinfunction "1_1") (pintype "passive"))
      (node (ref "J1") (pin "21") (pinfunction "21_21") (pintype "bidirectional"))
    )
    (net (code "38") (name "PREVGL") (class "Default")
      (node (ref "D4") (pin "2") (pinfunction "A_2") (pintype "bidirectional"))
      (node (ref "EPD_C11") (pin "1") (pinfunction "1_1") (pintype "passive"))
      (node (ref "J1") (pin "23") (pinfunction "23_23") (pintype "bidirectional"))
    )
    (net (code "39") (name "RESE") (class "Default")
      (node (ref "J1") (pin "3") (pinfunction "3_3") (pintype "bidirectional"))
      (node (ref "Q1") (pin "2") (pinfunction "S_2") (pintype "bidirectional"))
      (node (ref "R3") (pin "1") (pinfunction "1_1") (pintype "passive"))
    )
    (net (code "40") (name "RESE'") (class "Default")
      (node (ref "R2") (pin "2") (pinfunction "2_2") (pintype "passive"))
      (node (ref "R3") (pin "2") (pinfunction "2_2") (pintype "passive"))
      (node (ref "SJ1") (pin "2") (pinfunction "2_2") (pintype "passive"))
    )
    (net (code "41") (name "RESET") (class "Default")
      (node (ref "C5") (pin "1") (pinfunction "1_1") (pintype "passive"))
      (node (ref "IC1") (pin "1") (pinfunction "VOUT_1") (pintype "bidirectional"))
      (node (ref "RESET_BUTTON") (pin "3") (pinfunction "3_3") (pintype "passive"))
      (node (ref "RESET_BUTTON") (pin "4") (pinfunction "4_4") (pintype "passive"))
      (node (ref "R_RESET") (pin "2") (pinfunction "2_2") (pintype "passive"))
      (node (ref "U2") (pin "3") (pinfunction "EN_3") (pintype "input"))
    )
    (net (code "42") (name "RTC_RST") (class "Default")
      (node (ref "U2") (pin "16") (pinfunction "IO18_16") (pintype "bidirectional"))
      (node (ref "U3") (pin "4") (pinfunction "~{RST}_4") (pintype "input"))
    )
    (net (code "43") (name "RX") (class "Default")
      (node (ref "TP2") (pin "TP") (pinfunction "TP_TP") (pintype "input"))
      (node (ref "U2") (pin "24") (pinfunction "RXD0/GPIO17_24") (pintype "bidirectional"))
    )
    (net (code "44") (name "SCK") (class "Default")
      (node (ref "D10") (pin "2") (pinfunction "2_2") (pintype "passive"))
      (node (ref "J1") (pin "13") (pinfunction "13_13") (pintype "bidirectional"))
      (node (ref "J4") (pin "P5") (pinfunction "CLK_P5") (pintype "bidirectional"))
      (node (ref "R6") (pin "1") (pinfunction "1_1") (pintype "passive"))
      (node (ref "TP8") (pin "TP") (pinfunction "TP_TP") (pintype "input"))
      (node (ref "U1") (pin "6") (pinfunction "CLK_6") (pintype "input"))
      (node (ref "U2") (pin "6") (pinfunction "IO6_6") (pintype "bidirectional"))
    )
    (net (code "45") (name "SCL") (class "Default")
      (node (ref "J3") (pin "4") (pinfunction "4_4") (pintype "passive"))
      (node (ref "R2-PINH") (pin "1") (pinfunction "1_1") (pintype "passive"))
      (node (ref "SENSOR2") (pin "4") (pinfunction "SCK_4") (pintype "input"))
      (node (ref "U2") (pin "20") (pinfunction "IO22_20") (pintype "bidirectional"))
      (node (ref "U3") (pin "16") (pinfunction "SCL_16") (pintype "input"))
      (node (ref "U4") (pin "7") (pinfunction "SCL_7") (pintype "input"))
    )
    (net (code "46") (name "SDA") (class "Default")
      (node (ref "J3") (pin "3") (pinfunction "3_3") (pintype "passive"))
      (node (ref "R1_PINH") (pin "1") (pinfunction "1_1") (pintype "passive"))
      (node (ref "SENSOR2") (pin "3") (pinfunction "SDI_3") (pintype "bidirectional"))
      (node (ref "U2") (pin "19") (pinfunction "IO21_19") (pintype "bidirectional"))
      (node (ref "U3") (pin "15") (pinfunction "SDA_15") (pintype "bidirectional"))
      (node (ref "U4") (pin "8") (pinfunction "SDA_8") (pintype "bidirectional"))
    )
    (net (code "47") (name "SRC") (class "Default")
      (node (ref "C4") (pin "2") (pinfunction "2_2") (pintype "passive"))
      (node (ref "D5") (pin "2") (pinfunction "A_2") (pintype "bidirectional"))
      (node (ref "L1") (pin "1") (pinfunction "1_1") (pintype "passive"))
      (node (ref "Q1") (pin "3") (pinfunction "D_3") (pintype "bidirectional"))
    )
    (net (code "48") (name "SS_SD") (class "Default")
      (node (ref "D8") (pin "2") (pinfunction "2_2") (pintype "passive"))
      (node (ref "J4") (pin "P2") (pinfunction "CD/DAT3_P2") (pintype "bidirectional"))
      (node (ref "R10") (pin "1") (pinfunction "1_1") (pintype "passive"))
      (node (ref "U2") (pin "4") (pinfunction "IO4_4") (pintype "bidirectional"))
    )
    (net (code "49") (name "TX") (class "Default")
      (node (ref "TP1") (pin "TP") (pinfunction "TP_TP") (pintype "input"))
      (node (ref "U2") (pin "25") (pinfunction "TXD0/GPIO16_25") (pintype "bidirectional"))
    )
    (net (code "50") (name "USB_D+") (class "Default")
      (node (ref "D1") (pin "1") (pinfunction "I/O1_1_1") (pintype "bidirectional"))
      (node (ref "U2") (pin "14") (pinfunction "IO13_14") (pintype "bidirectional"))
    )
    (net (code "51") (name "USB_D-") (class "Default")
      (node (ref "D1") (pin "3") (pinfunction "I/O2_1_3") (pintype "bidirectional"))
      (node (ref "U2") (pin "13") (pinfunction "IO12_13") (pintype "bidirectional"))
    )
    (net (code "52") (name "VBAT") (class "Default")
      (node (ref "C2_BAT") (pin "1") (pinfunction "1_1") (pintype "passive"))
      (node (ref "MCP73831") (pin "3") (pinfunction "VBAT_3") (pintype "power_in"))
      (node (ref "Q3") (pin "3") (pinfunction "D_3") (pintype "bidirectional"))
      (node (ref "TP3") (pin "TP") (pinfunction "TP_TP") (pintype "input"))
      (node (ref "U4") (pin "2") (pinfunction "CELL_2") (pintype "power_in"))
      (node (ref "U4") (pin "3") (pinfunction "VDD_3") (pintype "power_in"))
    )
    (net (code "53") (name "VBUS") (class "Default")
      (node (ref "C1_BAT") (pin "1") (pinfunction "1_1") (pintype "passive"))
      (node (ref "C4_USB") (pin "1") (pinfunction "1_1") (pintype "passive"))
      (node (ref "C5_USB") (pin "1") (pinfunction "1_1") (pintype "passive"))
      (node (ref "CHG_LED") (pin "A") (pinfunction "A_A") (pintype "passive"))
      (node (ref "D1") (pin "5") (pinfunction "VBUS_5") (pintype "bidirectional"))
      (node (ref "D2") (pin "2") (pinfunction "ANODE_2") (pintype "bidirectional"))
      (node (ref "MCP73831") (pin "4") (pinfunction "VIN_4") (pintype "power_in"))
      (node (ref "PFMF.050.1") (pin "2") (pinfunction "2_2") (pintype "passive"))
      (node (ref "Q3") (pin "1") (pinfunction "G_1") (pintype "bidirectional"))
      (node (ref "R1_PWRUSB") (pin "2") (pinfunction "2_2") (pintype "passive"))
      (node (ref "TP14") (pin "TP") (pinfunction "TP_TP") (pintype "input"))
    )
    (net (code "54") (name "VRTC") (class "Default")
      (node (ref "C10_SUPERCAP") (pin "1") (pinfunction "1_1") (pintype "passive"))
      (node (ref "C8") (pin "1") (pinfunction "1_1") (pintype "passive"))
      (node (ref "R_CAPACITOR") (pin "1") (pinfunction "1_1") (pintype "passive"))
      (node (ref "U3") (pin "14") (pinfunction "VBAT_14") (pintype "power_in"))
    )
    (net (code "55") (name "VUSB") (class "Default")
      (node (ref "J2") (pin "A4") (pinfunction "A4_A4") (pintype "bidirectional"))
      (node (ref "J2") (pin "A9") (pinfunction "A9_A9") (pintype "bidirectional"))
      (node (ref "J2") (pin "B4") (pinfunction "B4_B4") (pintype "bidirectional"))
      (node (ref "J2") (pin "B9") (pinfunction "B9_B9") (pintype "bidirectional"))
      (node (ref "PFMF.050.1") (pin "1") (pinfunction "1_1") (pintype "passive"))
    )
    (net (code "56") (name "unconnected-(IC1-NC-Pad4)") (class "Default")
      (node (ref "IC1") (pin "4") (pinfunction "NC_4") (pintype "no_connect"))
    )
    (net (code "57") (name "unconnected-(IC2-NC-Pad4)") (class "Default")
      (node (ref "IC2") (pin "4") (pinfunction "NC_4") (pintype "no_connect"))
    )
    (net (code "58") (name "unconnected-(J1-Pad1)") (class "Default")
      (node (ref "J1") (pin "1") (pinfunction "1_1") (pintype "bidirectional"))
    )
    (net (code "59") (name "unconnected-(J1-Pad6)") (class "Default")
      (node (ref "J1") (pin "6") (pinfunction "6_6") (pintype "bidirectional"))
    )
    (net (code "60") (name "unconnected-(J1-Pad7)") (class "Default")
      (node (ref "J1") (pin "7") (pinfunction "7_7") (pintype "bidirectional"))
    )
    (net (code "61") (name "unconnected-(J2-PadA8)") (class "Default")
      (node (ref "J2") (pin "A8") (pinfunction "A8_A8") (pintype "bidirectional"))
    )
    (net (code "62") (name "unconnected-(J2-PadB8)") (class "Default")
      (node (ref "J2") (pin "B8") (pinfunction "B8_B8") (pintype "bidirectional"))
    )
    (net (code "63") (name "unconnected-(J4-DAT1-PadP8)") (class "Default")
      (node (ref "J4") (pin "P8") (pinfunction "DAT1_P8") (pintype "bidirectional"))
    )
    (net (code "64") (name "unconnected-(J4-DAT2-PadP1)") (class "Default")
      (node (ref "J4") (pin "P1") (pinfunction "DAT2_P1") (pintype "bidirectional"))
    )
    (net (code "65") (name "unconnected-(J4-DETECTION_1-PadS1)") (class "Default")
      (node (ref "J4") (pin "S1") (pinfunction "DETECTION_1_S1") (pintype "bidirectional"))
    )
    (net (code "66") (name "unconnected-(J4-DETECTION_2-PadS2)") (class "Default")
      (node (ref "J4") (pin "S2") (pinfunction "DETECTION_2_S2") (pintype "bidirectional"))
    )
    (net (code "67") (name "unconnected-(U2-NC-Pad22)") (class "Default")
      (node (ref "U2") (pin "22") (pinfunction "NC_22") (pintype "no_connect"))
    )
    (net (code "68") (name "unconnected-(U4-~{ALERT}-Pad5)") (class "Default")
      (node (ref "U4") (pin "5") (pinfunction "~{ALERT}_5") (pintype "output"))
    )
  )
)
